# TEST_HJ-185.net
KiCad netlist of a schematic drawn in Altium Designer
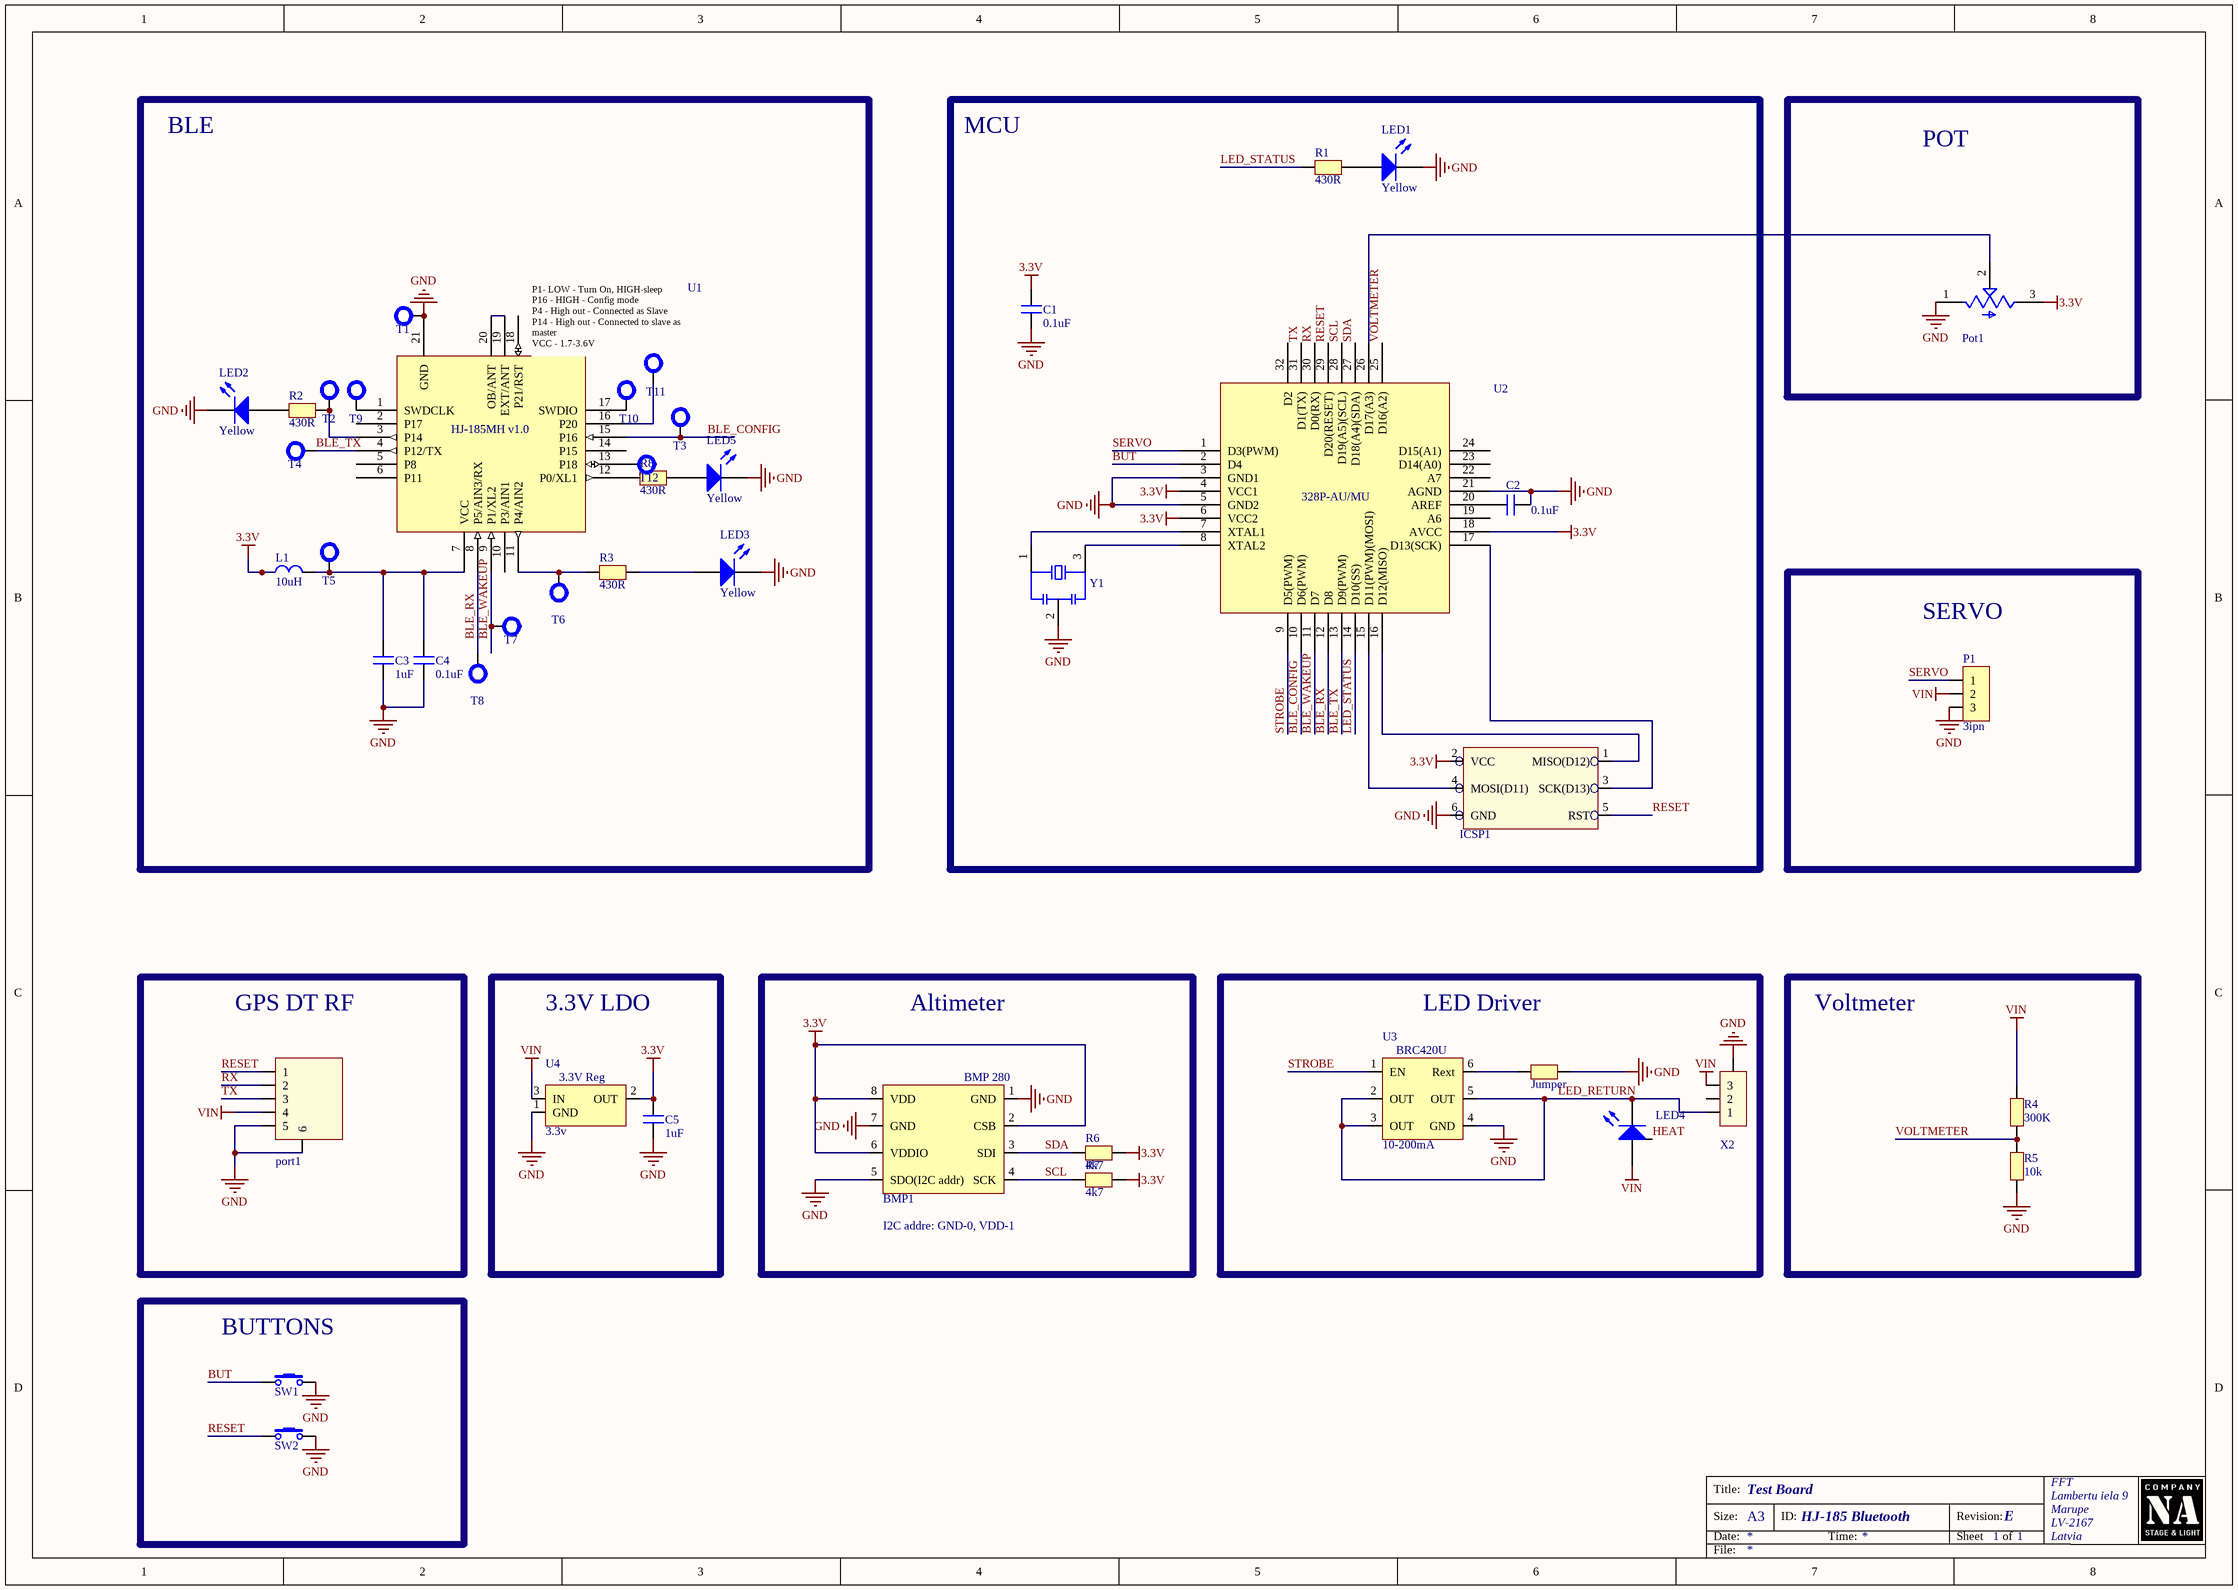
[diagram p0: TEST_HJ-185.SchDoc]

(export (version "E")
  (design (tool "Eeschema 10.0.6"))
  (components
    (comp (ref "BMP1")
      (value "± 0.12 hPa equivalent to ±1 m")
      (footprint "BMP280")
      (description "Pressure sensor")
      (fields (field (name "MANUFACTURER") "BOSCH") (field (name "PART NUMBER") "828-1064-1-ND - BMP 280"))
      (libsource (lib "My_Storage") (part "BMP 280"))
    )
    (comp (ref "C1")
      (value "0.1uF")
      (footprint "FFT:C0603-FFT")
      (description "C0603_0.1uF_50V")
      (fields (field (name "PART NUMBER") "CC0603KRX7R9BB104") (field (name "MANUFACTURER") "YAEGO"))
      (libsource (lib "LCSC") (part "C0603_0.1uF_50V"))
    )
    (comp (ref "C2")
      (value "0.1uF")
      (footprint "FFT:C0603-FFT")
      (description "C0603_0.1uF_50V")
      (fields (field (name "PART NUMBER") "CC0603KRX7R9BB104") (field (name "MANUFACTURER") "YAEGO"))
      (libsource (lib "LCSC") (part "C0603_0.1uF_50V"))
    )
    (comp (ref "C3")
      (value "1uF")
      (footprint "FFT:C0603-FFT")
      (description "C0603_1uF_25V")
      (fields (field (name "PART NUMBER") "CL10A105KB8NNNC") (field (name "MANUFACTURER") "SAMSUNG"))
      (libsource (lib "LCSC") (part "C0603_1uF_25V"))
    )
    (comp (ref "C4")
      (value "0.1uF")
      (footprint "FFT:C0603-FFT")
      (description "C0603_0.1uF_50V")
      (fields (field (name "PART NUMBER") "CC0603KRX7R9BB104") (field (name "MANUFACTURER") "YAEGO"))
      (libsource (lib "LCSC") (part "C0603_0.1uF_50V"))
    )
    (comp (ref "C5")
      (value "1uF")
      (footprint "FFT:C0603-FFT")
      (description "C0603_1uF_25V")
      (fields (field (name "PART NUMBER") "CL10A105KB8NNNC") (field (name "MANUFACTURER") "SAMSUNG"))
      (libsource (lib "LCSC") (part "C0603_1uF_25V"))
    )
    (comp (ref "ICSP1")
      (value "Progr ICSP")
      (footprint "ICSP prg PIN 2.54mm")
      (description "PAD prog")
      (libsource (lib "FFT") (part "Progr ICSP"))
    )
    (comp (ref "L1")
      (value "10uH")
      (footprint "FFT:L0603")
      (description "Inductor")
      (fields (field (name "PART NUMBER") "222") (field (name "MANUFACTURER") "Aliexpress"))
      (libsource (lib "FFT") (part "L0603_10uH"))
    )
    (comp (ref "LED1")
      (value "Yellow")
      (footprint "FFT:LED0603")
      (description "LED 0603 chip")
      (fields
        (field (name "MANUFACTURER") "Everlight Elec")
        (field (name "PART NUMBER") "19-213/Y2C-CQ2R2L/3T(CY)")
      )
      (libsource (lib "My_Storage") (part "19-213/Y2C-CQ2R2L/3T(CY)"))
    )
    (comp (ref "LED2")
      (value "Yellow")
      (footprint "FFT:LED0603")
      (description "LED 0603 chip")
      (fields
        (field (name "MANUFACTURER") "Everlight Elec")
        (field (name "PART NUMBER") "19-213/Y2C-CQ2R2L/3T(CY)")
      )
      (libsource (lib "My_Storage") (part "19-213/Y2C-CQ2R2L/3T(CY)"))
    )
    (comp (ref "LED3")
      (value "Yellow")
      (footprint "FFT:LED0603")
      (description "LED 0603 chip")
      (fields
        (field (name "MANUFACTURER") "Everlight Elec")
        (field (name "PART NUMBER") "19-213/Y2C-CQ2R2L/3T(CY)")
      )
      (libsource (lib "My_Storage") (part "19-213/Y2C-CQ2R2L/3T(CY)"))
    )
    (comp (ref "LED4")
      (value "Cool White")
      (footprint "CREE XPL")
      (description "LED")
      (fields (field (name "MANUFACTURER") "CREE") (field (name "PART NUMBER") "XPL"))
      (libsource (lib "FFT") (part "XPL"))
    )
    (comp (ref "LED5")
      (value "Yellow")
      (footprint "FFT:LED0603")
      (description "LED 0603 chip")
      (fields
        (field (name "MANUFACTURER") "Everlight Elec")
        (field (name "PART NUMBER") "19-213/Y2C-CQ2R2L/3T(CY)")
      )
      (libsource (lib "My_Storage") (part "19-213/Y2C-CQ2R2L/3T(CY)"))
    )
    (comp (ref "P1")
      (value "3ipn")
      (footprint "FFT:HDR1x3")
      (description "Header 3x1-PIN, 2.54mm")
      (fields (field (name "MANUFACTURER") "Connfly") (field (name "PART NUMBER") "DS1021-1*3SF1-1"))
      (libsource (lib "FFT") (part "Header 3x1"))
    )
    (comp (ref "port1")
      (value "1.0mm 5pin")
      (footprint "JST 5pin 1mm")
      (description "Connector 5p hor 1mm")
      (fields (field (name "MANUFACTURER") "JST") (field (name "PART NUMBER") "SM05B-SRSS-TB"))
      (libsource (lib "FFT") (part "SM05B-SRSS-TB"))
    )
    (comp (ref "Pot1")
      (value "TC33X-10K")
      (footprint "TrimPot - TC33X-2-101G")
      (description "TrimPot SMD")
      (fields (field (name "MANUFACTURER") "BOURNS"))
      (libsource (lib "My_Storage") (part "TC33X-10K"))
    )
    (comp (ref "R1")
      (value "430R")
      (footprint "FFT:R0603-FFT")
      (description "SMD resistor")
      (fields (field (name "PART NUMBER") "0603WAF4300T5E") (field (name "MANUFACTURER") "Uniroyal Elec"))
      (libsource (lib "") (part "R0603_430_2"))
    )
    (comp (ref "R2")
      (value "430R")
      (footprint "FFT:R0603-FFT")
      (description "SMD resistor")
      (fields (field (name "PART NUMBER") "0603WAF4300T5E") (field (name "MANUFACTURER") "Uniroyal Elec"))
      (libsource (lib "LCSC") (part "R0603_430"))
    )
    (comp (ref "R3")
      (value "430R")
      (footprint "FFT:R0603-FFT")
      (description "SMD resistor")
      (fields (field (name "PART NUMBER") "0603WAF4300T5E") (field (name "MANUFACTURER") "Uniroyal Elec"))
      (libsource (lib "") (part "R0603_430_2"))
    )
    (comp (ref "R4")
      (value "300K")
      (footprint "FFT:R0603-FFT")
      (description "SMD resistor")
      (fields (field (name "PART NUMBER") "0603WAF3003T5E") (field (name "MANUFACTURER") "Uniroyal Elec"))
      (libsource (lib "LCSC") (part "R0603_300k"))
    )
    (comp (ref "R5")
      (value "10k")
      (footprint "FFT:R0603-FFT")
      (description "SMD resistor")
      (fields (field (name "PART NUMBER") "0603WAF1002T5E") (field (name "MANUFACTURER") "Uniroyal Elec"))
      (libsource (lib "LCSC") (part "R0603_10k"))
    )
    (comp (ref "R6")
      (value "4k7")
      (footprint "FFT:R0603-FFT")
      (description "SMD resistor")
      (fields (field (name "PART NUMBER") "SMD0603-4K7-1%") (field (name "MANUFACTURER") "Yageo"))
      (libsource (lib "LCSC") (part "R0603_4k7"))
    )
    (comp (ref "R7")
      (value "4k7")
      (footprint "FFT:R0603-FFT")
      (description "SMD resistor")
      (fields (field (name "PART NUMBER") "SMD0603-4K7-1%") (field (name "MANUFACTURER") "Yageo"))
      (libsource (lib "LCSC") (part "R0603_4k7"))
    )
    (comp (ref "R8")
      (value "430R")
      (footprint "FFT:R0603-FFT")
      (description "SMD resistor")
      (fields (field (name "PART NUMBER") "0603WAF4300T5E") (field (name "MANUFACTURER") "Uniroyal Elec"))
      (libsource (lib "") (part "R0603_430_1"))
    )
    (comp (ref "SW1")
      (value "~")
      (footprint "Switch Tactile SKRPACE010")
      (description "Switch Tactile")
      (fields (field (name "MANUFACTURER") "ALPS") (field (name "PART NUMBER") "SKRPACE010"))
      (libsource (lib "My_Storage") (part "SKRPACE010"))
    )
    (comp (ref "SW2")
      (value "~")
      (footprint "Switch Tactile TS-1088C")
      (description "Switch Tactile")
      (fields (field (name "MANUFACTURER") "XUNPU") (field (name "PART NUMBER") "TS-1088C-02526"))
      (libsource (lib "My_Storage") (part "TS-1088C-02526"))
    )
    (comp (ref "T1")
      (value "?")
      (footprint "FFT:Test Point")
      (description "Test Point")
      (fields (field (name "PART NUMBER") "C0402"))
      (libsource (lib "FFT") (part "Test Point"))
    )
    (comp (ref "T2")
      (value "?")
      (footprint "FFT:Test Point")
      (description "Test Point")
      (fields (field (name "PART NUMBER") "C0402"))
      (libsource (lib "FFT") (part "Test Point"))
    )
    (comp (ref "T3")
      (value "?")
      (footprint "FFT:Test Point")
      (description "Test Point")
      (fields (field (name "PART NUMBER") "C0402"))
      (libsource (lib "FFT") (part "Test Point"))
    )
    (comp (ref "T4")
      (value "?")
      (footprint "FFT:Test Point")
      (description "Test Point")
      (fields (field (name "PART NUMBER") "C0402"))
      (libsource (lib "FFT") (part "Test Point"))
    )
    (comp (ref "T5")
      (value "?")
      (footprint "FFT:Test Point")
      (description "Test Point")
      (fields (field (name "PART NUMBER") "C0402"))
      (libsource (lib "FFT") (part "Test Point"))
    )
    (comp (ref "T6")
      (value "?")
      (footprint "FFT:Test Point")
      (description "Test Point")
      (fields (field (name "PART NUMBER") "C0402"))
      (libsource (lib "FFT") (part "Test Point"))
    )
    (comp (ref "T7")
      (value "?")
      (footprint "FFT:Test Point")
      (description "Test Point")
      (fields (field (name "PART NUMBER") "C0402"))
      (libsource (lib "FFT") (part "Test Point"))
    )
    (comp (ref "T8")
      (value "?")
      (footprint "FFT:Test Point")
      (description "Test Point")
      (fields (field (name "PART NUMBER") "C0402"))
      (libsource (lib "FFT") (part "Test Point"))
    )
    (comp (ref "T9")
      (value "?")
      (footprint "FFT:Test Point")
      (description "Test Point")
      (fields (field (name "PART NUMBER") "C0402"))
      (libsource (lib "FFT") (part "Test Point"))
    )
    (comp (ref "T10")
      (value "?")
      (footprint "FFT:Test Point")
      (description "Test Point")
      (fields (field (name "PART NUMBER") "C0402"))
      (libsource (lib "FFT") (part "Test Point"))
    )
    (comp (ref "T11")
      (value "?")
      (footprint "FFT:Test Point")
      (description "Test Point")
      (fields (field (name "PART NUMBER") "C0402"))
      (libsource (lib "FFT") (part "Test Point"))
    )
    (comp (ref "T12")
      (value "?")
      (footprint "FFT:Test Point")
      (description "Test Point")
      (fields (field (name "PART NUMBER") "C0402"))
      (libsource (lib "FFT") (part "Test Point"))
    )
    (comp (ref "U1")
      (value "~")
      (footprint "LGA-24-fft")
      (description "Module BLE")
      (fields (field (name "PART NUMBER") "HJ-185IMH_SPPv2") (field (name "MANUFACTURER") "tshjdz.com"))
      (libsource (lib "My_Storage") (part "HJ-185MH"))
    )
    (comp (ref "U2")
      (value "~")
      (footprint "32-pin QFP 10mm")
      (description "MCU")
      (fields (field (name "PART NUMBER") "ATmega 328p-AU") (field (name "MANUFACTURER") "Microchip Tech"))
      (libsource (lib "My_Storage") (part "Atmega 328P-AU"))
    )
    (comp (ref "U3")
      (value "10-200mA")
      (footprint "FFT:SC74")
      (description "LED Driver 10-200mA")
      (fields (field (name "MANUFACTURER") "Infeon") (field (name "PART NUMBER") "BCR421UE6327"))
      (libsource (lib "My_Storage") (part "BRC420U"))
    )
    (comp (ref "U4")
      (value "3.3v")
      (footprint "SOT23-3")
      (description "LDO 3.3V 300mA")
      (fields (field (name "PART NUMBER") "MIC5209") (field (name "MANUFACTURER") "DIODES INCORPORATED"))
      (libsource (lib "FFT") (part "AP2210N-3.3TRG1"))
    )
    (comp (ref "X1")
      (value "Jumper")
      (footprint "0603 clear pad")
      (description "Pad")
      (fields (field (name "PART NUMBER") "1212") (field (name "MANUFACTURER") "clear pad"))
      (libsource (lib "FFT") (part "Jumper 0603"))
    )
    (comp (ref "X2")
      (value "1.0mm 3pin")
      (footprint "JST 3pin 1mm")
      (description "Connector 3p hor 1mm")
      (fields (field (name "MANUFACTURER") "JST") (field (name "PART NUMBER") "SM05B-SRSS-TB"))
      (libsource (lib "My_Storage") (part "SM03B-SRSS-TB"))
    )
    (comp (ref "Y1")
      (value "CSTCE8M0V53-R0")
      (footprint "OSC_CSTCE16M0V53-R0")
      (description "Ceramic Resonator 8Mhz")
      (fields (field (name "MANUFACTURER") "Murata") (field (name "PART NUMBER") "CSTCE8M0V53-R0_1"))
      (libsource (lib "My_Storage") (part "CSTCE8M0V53-R0"))
    )
  )
  (nets
    (net (code "1") (name "/BLE_CONFIG") (class "Default")
      (node (ref "T3") (pin "1") (pintype "passive"))
      (node (ref "U1") (pin "15") (pinfunction "P16_15") (pintype "input"))
      (node (ref "U2") (pin "10") (pinfunction "D6(PWM)_10") (pintype "passive"))
    )
    (net (code "2") (name "/BLE_RX") (class "Default")
      (node (ref "T8") (pin "1") (pintype "passive"))
      (node (ref "U1") (pin "8") (pinfunction "P5/AIN3/RX_8") (pintype "input"))
      (node (ref "U2") (pin "12") (pinfunction "D8_12") (pintype "passive"))
    )
    (net (code "3") (name "/BLE_TX") (class "Default")
      (node (ref "T4") (pin "1") (pintype "passive"))
      (node (ref "U1") (pin "4") (pinfunction "P12/TX_4") (pintype "output"))
      (node (ref "U2") (pin "13") (pinfunction "D9(PWM)_13") (pintype "passive"))
    )
    (net (code "4") (name "/BLE_WAKEUP") (class "Default")
      (node (ref "T7") (pin "1") (pintype "passive"))
      (node (ref "U1") (pin "9") (pinfunction "P1/XL2_9") (pintype "input"))
      (node (ref "U2") (pin "11") (pinfunction "D7_11") (pintype "passive"))
    )
    (net (code "5") (name "/BUT") (class "Default")
      (node (ref "SW1") (pin "1") (pinfunction "1_1") (pintype "passive"))
      (node (ref "U2") (pin "2") (pinfunction "D4_2") (pintype "passive"))
    )
    (net (code "6") (name "/HEAT") (class "Default")
      (node (ref "LED4") (pin "PAD") (pinfunction "P_PAD") (pintype "passive"))
    )
    (net (code "7") (name "/LED_RETURN") (class "Default")
      (node (ref "LED4") (pin "K") (pinfunction "K_K") (pintype "passive"))
      (node (ref "U3") (pin "2") (pinfunction "OUT_2") (pintype "passive"))
      (node (ref "U3") (pin "3") (pinfunction "OUT_3") (pintype "passive"))
      (node (ref "U3") (pin "5") (pinfunction "OUT_5") (pintype "passive"))
      (node (ref "X2") (pin "1") (pinfunction "1_1") (pintype "passive"))
    )
    (net (code "8") (name "/LED_STATUS") (class "Default")
      (node (ref "R1") (pin "1") (pinfunction "1_1") (pintype "passive"))
      (node (ref "U2") (pin "14") (pinfunction "D10(SS)_14") (pintype "passive"))
    )
    (net (code "9") (name "/RESET") (class "Default")
      (node (ref "ICSP1") (pin "5") (pinfunction "RST_5") (pintype "passive"))
      (node (ref "SW2") (pin "1") (pinfunction "1_1") (pintype "passive"))
      (node (ref "U2") (pin "29") (pinfunction "D20(RESET)_29") (pintype "passive"))
      (node (ref "port1") (pin "1") (pinfunction "1_1") (pintype "passive"))
    )
    (net (code "10") (name "/RX") (class "Default")
      (node (ref "U2") (pin "30") (pinfunction "D0(RX)_30") (pintype "passive"))
      (node (ref "port1") (pin "2") (pinfunction "2_2") (pintype "passive"))
    )
    (net (code "11") (name "/SCL") (class "Default")
      (node (ref "BMP1") (pin "4") (pinfunction "SCK_4") (pintype "passive"))
      (node (ref "R7") (pin "1") (pinfunction "1_1") (pintype "passive"))
      (node (ref "U2") (pin "28") (pinfunction "D19(A5)(SCL)_28") (pintype "passive"))
    )
    (net (code "12") (name "/SDA") (class "Default")
      (node (ref "BMP1") (pin "3") (pinfunction "SDI_3") (pintype "passive"))
      (node (ref "R6") (pin "1") (pinfunction "1_1") (pintype "passive"))
      (node (ref "U2") (pin "27") (pinfunction "D18(A4)(SDA)_27") (pintype "passive"))
    )
    (net (code "13") (name "/SERVO") (class "Default")
      (node (ref "P1") (pin "1") (pinfunction "1_1") (pintype "passive"))
      (node (ref "U2") (pin "1") (pinfunction "D3(PWM)_1") (pintype "passive"))
    )
    (net (code "14") (name "/STROBE") (class "Default")
      (node (ref "U2") (pin "9") (pinfunction "D5(PWM)_9") (pintype "passive"))
      (node (ref "U3") (pin "1") (pinfunction "EN_1") (pintype "passive"))
    )
    (net (code "15") (name "/TX") (class "Default")
      (node (ref "U2") (pin "31") (pinfunction "D1(TX)_31") (pintype "passive"))
      (node (ref "port1") (pin "3") (pinfunction "3_3") (pintype "passive"))
    )
    (net (code "16") (name "/VOLTMETER") (class "Default")
      (node (ref "R4") (pin "1") (pinfunction "1_1") (pintype "passive"))
      (node (ref "R5") (pin "2") (pinfunction "2_2") (pintype "passive"))
      (node (ref "U2") (pin "25") (pinfunction "D16(A2)_25") (pintype "passive"))
    )
    (net (code "17") (name "3.3V") (class "Default")
      (node (ref "BMP1") (pin "2") (pinfunction "CSB_2") (pintype "passive"))
      (node (ref "BMP1") (pin "6") (pinfunction "VDDIO_6") (pintype "passive"))
      (node (ref "BMP1") (pin "8") (pinfunction "VDD_8") (pintype "passive"))
      (node (ref "C1") (pin "2") (pintype "passive"))
      (node (ref "C5") (pin "2") (pintype "passive"))
      (node (ref "ICSP1") (pin "2") (pinfunction "VCC_2") (pintype "passive"))
      (node (ref "L1") (pin "1") (pinfunction "1_1") (pintype "passive"))
      (node (ref "Pot1") (pin "3") (pinfunction "CW_3") (pintype "passive"))
      (node (ref "R6") (pin "2") (pinfunction "2_2") (pintype "passive"))
      (node (ref "R7") (pin "2") (pinfunction "2_2") (pintype "passive"))
      (node (ref "U2") (pin "18") (pinfunction "AVCC_18") (pintype "passive"))
      (node (ref "U2") (pin "4") (pinfunction "VCC1_4") (pintype "passive"))
      (node (ref "U2") (pin "6") (pinfunction "VCC2_6") (pintype "passive"))
      (node (ref "U4") (pin "2") (pinfunction "OUT_2") (pintype "passive"))
    )
    (net (code "18") (name "GND") (class "Default")
      (node (ref "BMP1") (pin "1") (pinfunction "GND_1") (pintype "passive"))
      (node (ref "BMP1") (pin "5") (pinfunction "SDO(I2C_addr)_5") (pintype "passive"))
      (node (ref "BMP1") (pin "7") (pinfunction "GND_7") (pintype "passive"))
      (node (ref "C1") (pin "1") (pintype "passive"))
      (node (ref "C2") (pin "2") (pintype "passive"))
      (node (ref "C3") (pin "1") (pintype "passive"))
      (node (ref "C4") (pin "1") (pintype "passive"))
      (node (ref "C5") (pin "1") (pintype "passive"))
      (node (ref "ICSP1") (pin "6") (pinfunction "GND_6") (pintype "passive"))
      (node (ref "LED1") (pin "C") (pinfunction "C_C") (pintype "passive"))
      (node (ref "LED2") (pin "C") (pinfunction "C_C") (pintype "passive"))
      (node (ref "LED3") (pin "C") (pinfunction "C_C") (pintype "passive"))
      (node (ref "LED5") (pin "C") (pinfunction "C_C") (pintype "passive"))
      (node (ref "P1") (pin "3") (pinfunction "3_3") (pintype "passive"))
      (node (ref "Pot1") (pin "1") (pinfunction "CCW_1") (pintype "passive"))
      (node (ref "R5") (pin "1") (pinfunction "1_1") (pintype "passive"))
      (node (ref "SW1") (pin "2") (pinfunction "2_2") (pintype "passive"))
      (node (ref "SW2") (pin "2") (pinfunction "2_2") (pintype "passive"))
      (node (ref "T1") (pin "1") (pintype "passive"))
      (node (ref "U1") (pin "21") (pinfunction "GND_21") (pintype "passive"))
      (node (ref "U2") (pin "21") (pinfunction "AGND_21") (pintype "passive"))
      (node (ref "U2") (pin "3") (pinfunction "GND1_3") (pintype "passive"))
      (node (ref "U2") (pin "5") (pinfunction "GND2_5") (pintype "passive"))
      (node (ref "U3") (pin "4") (pinfunction "GND_4") (pintype "passive"))
      (node (ref "U4") (pin "1") (pinfunction "GND_1") (pintype "power_in"))
      (node (ref "X1") (pin "1") (pintype "passive"))
      (node (ref "X2") (pin "6") (pinfunction "GND_6") (pintype "passive"))
      (node (ref "Y1") (pin "2") (pinfunction "OSC2_2") (pintype "passive"))
      (node (ref "port1") (pin "5") (pinfunction "5_5") (pintype "passive"))
      (node (ref "port1") (pin "6") (pinfunction "6_6") (pintype "passive"))
    )
    (net (code "19") (name "Net-(ICSP1-MISO(D12))") (class "Default")
      (node (ref "ICSP1") (pin "1") (pinfunction "MISO(D12)_1") (pintype "passive"))
      (node (ref "U2") (pin "16") (pinfunction "D12(MISO)_16") (pintype "passive"))
    )
    (net (code "20") (name "Net-(ICSP1-MOSI(D11))") (class "Default")
      (node (ref "ICSP1") (pin "4") (pinfunction "MOSI(D11)_4") (pintype "passive"))
      (node (ref "U2") (pin "15") (pinfunction "D11(PWM)(MOSI)_15") (pintype "passive"))
    )
    (net (code "21") (name "Net-(ICSP1-SCK(D13))") (class "Default")
      (node (ref "ICSP1") (pin "3") (pinfunction "SCK(D13)_3") (pintype "passive"))
      (node (ref "U2") (pin "17") (pinfunction "D13(SCK)_17") (pintype "passive"))
    )
    (net (code "22") (name "Net-(LED1-PadA)") (class "Default")
      (node (ref "LED1") (pin "A") (pinfunction "A_A") (pintype "passive"))
      (node (ref "R1") (pin "2") (pinfunction "2_2") (pintype "passive"))
    )
    (net (code "23") (name "Net-(LED2-PadA)") (class "Default")
      (node (ref "LED2") (pin "A") (pinfunction "A_A") (pintype "passive"))
      (node (ref "R2") (pin "2") (pinfunction "2_2") (pintype "passive"))
    )
    (net (code "24") (name "Net-(LED3-PadA)") (class "Default")
      (node (ref "LED3") (pin "A") (pinfunction "A_A") (pintype "passive"))
      (node (ref "R3") (pin "2") (pinfunction "2_2") (pintype "passive"))
    )
    (net (code "25") (name "Net-(LED5-PadA)") (class "Default")
      (node (ref "LED5") (pin "A") (pinfunction "A_A") (pintype "passive"))
      (node (ref "R8") (pin "2") (pinfunction "2_2") (pintype "passive"))
    )
    (net (code "26") (name "Net-(Pot1-W)") (class "Default")
      (node (ref "Pot1") (pin "2") (pinfunction "W_2") (pintype "passive"))
      (node (ref "U2") (pin "26") (pinfunction "D17(A3)_26") (pintype "passive"))
    )
    (net (code "27") (name "Net-(U1-EXT{slash}ANT)") (class "Default")
      (node (ref "U1") (pin "19") (pinfunction "EXT/ANT_19") (pintype "passive"))
      (node (ref "U1") (pin "20") (pinfunction "OB/ANT_20") (pintype "passive"))
    )
    (net (code "28") (name "Net-(U1-P0{slash}XL1)") (class "Default")
      (node (ref "R8") (pin "1") (pinfunction "1_1") (pintype "passive"))
      (node (ref "U1") (pin "12") (pinfunction "P0/XL1_12") (pintype "output"))
    )
    (net (code "29") (name "Net-(U1-P4{slash}AIN2)") (class "Default")
      (node (ref "R3") (pin "1") (pinfunction "1_1") (pintype "passive"))
      (node (ref "T6") (pin "1") (pintype "passive"))
      (node (ref "U1") (pin "11") (pinfunction "P4/AIN2_11") (pintype "output"))
    )
    (net (code "30") (name "Net-(U1-P14)") (class "Default")
      (node (ref "R2") (pin "1") (pinfunction "1_1") (pintype "passive"))
      (node (ref "T2") (pin "1") (pintype "passive"))
      (node (ref "U1") (pin "3") (pinfunction "P14_3") (pintype "output"))
    )
    (net (code "31") (name "Net-(U1-P18)") (class "Default")
      (node (ref "T12") (pin "1") (pintype "passive"))
      (node (ref "U1") (pin "13") (pinfunction "P18_13") (pintype "bidirectional"))
    )
    (net (code "32") (name "Net-(U1-P20)") (class "Default")
      (node (ref "T11") (pin "1") (pintype "passive"))
      (node (ref "U1") (pin "16") (pinfunction "P20_16") (pintype "passive"))
    )
    (net (code "33") (name "Net-(U1-SWDCLK)") (class "Default")
      (node (ref "T9") (pin "1") (pintype "passive"))
      (node (ref "U1") (pin "1") (pinfunction "SWDCLK_1") (pintype "passive"))
    )
    (net (code "34") (name "Net-(U1-SWDIO)") (class "Default")
      (node (ref "T10") (pin "1") (pintype "passive"))
      (node (ref "U1") (pin "17") (pinfunction "SWDIO_17") (pintype "passive"))
    )
    (net (code "35") (name "Net-(U1-VCC)") (class "Default")
      (node (ref "C3") (pin "2") (pintype "passive"))
      (node (ref "C4") (pin "2") (pintype "passive"))
      (node (ref "L1") (pin "2") (pinfunction "2_2") (pintype "passive"))
      (node (ref "T5") (pin "1") (pintype "passive"))
      (node (ref "U1") (pin "7") (pinfunction "VCC_7") (pintype "power_in"))
    )
    (net (code "36") (name "Net-(U2-AREF)") (class "Default")
      (node (ref "C2") (pin "1") (pintype "passive"))
      (node (ref "U2") (pin "20") (pinfunction "AREF_20") (pintype "passive"))
    )
    (net (code "37") (name "Net-(U2-XTAL1)") (class "Default")
      (node (ref "U2") (pin "7") (pinfunction "XTAL1_7") (pintype "passive"))
      (node (ref "Y1") (pin "1") (pinfunction "OSC1_1") (pintype "passive"))
    )
    (net (code "38") (name "Net-(U2-XTAL2)") (class "Default")
      (node (ref "U2") (pin "8") (pinfunction "XTAL2_8") (pintype "passive"))
      (node (ref "Y1") (pin "3") (pinfunction "OSC3_3") (pintype "passive"))
    )
    (net (code "39") (name "Net-(U3-Rext)") (class "Default")
      (node (ref "U3") (pin "6") (pinfunction "Rext_6") (pintype "passive"))
      (node (ref "X1") (pin "2") (pintype "passive"))
    )
    (net (code "40") (name "VIN") (class "Default")
      (node (ref "LED4") (pin "A") (pinfunction "A_A") (pintype "passive"))
      (node (ref "P1") (pin "2") (pinfunction "2_2") (pintype "passive"))
      (node (ref "R4") (pin "2") (pinfunction "2_2") (pintype "passive"))
      (node (ref "U4") (pin "3") (pinfunction "IN_3") (pintype "power_in"))
      (node (ref "X2") (pin "3") (pinfunction "3_3") (pintype "passive"))
      (node (ref "port1") (pin "4") (pinfunction "4_4") (pintype "passive"))
    )
    (net (code "41") (name "unconnected-(U1-P3{slash}AIN1-Pad10)") (class "Default")
      (node (ref "U1") (pin "10") (pinfunction "P3/AIN1_10") (pintype "passive"))
    )
    (net (code "42") (name "unconnected-(U1-P8-Pad5)") (class "Default")
      (node (ref "U1") (pin "5") (pinfunction "P8_5") (pintype "passive"))
    )
    (net (code "43") (name "unconnected-(U1-P11-Pad6)") (class "Default")
      (node (ref "U1") (pin "6") (pinfunction "P11_6") (pintype "passive"))
    )
    (net (code "44") (name "unconnected-(U1-P15-Pad14)") (class "Default")
      (node (ref "U1") (pin "14") (pinfunction "P15_14") (pintype "passive"))
    )
    (net (code "45") (name "unconnected-(U1-P17-Pad2)") (class "Default")
      (node (ref "U1") (pin "2") (pinfunction "P17_2") (pintype "passive"))
    )
    (net (code "46") (name "unconnected-(U1-P21{slash}RST-Pad18)") (class "Default")
      (node (ref "U1") (pin "18") (pinfunction "P21/RST_18") (pintype "bidirectional"))
    )
    (net (code "47") (name "unconnected-(U2-A6-Pad19)") (class "Default")
      (node (ref "U2") (pin "19") (pinfunction "A6_19") (pintype "passive"))
    )
    (net (code "48") (name "unconnected-(U2-A7-Pad22)") (class "Default")
      (node (ref "U2") (pin "22") (pinfunction "A7_22") (pintype "passive"))
    )
    (net (code "49") (name "unconnected-(U2-D2-Pad32)") (class "Default")
      (node (ref "U2") (pin "32") (pinfunction "D2_32") (pintype "passive"))
    )
    (net (code "50") (name "unconnected-(U2-D14(A0)-Pad23)") (class "Default")
      (node (ref "U2") (pin "23") (pinfunction "D14(A0)_23") (pintype "passive"))
    )
    (net (code "51") (name "unconnected-(U2-D15(A1)-Pad24)") (class "Default")
      (node (ref "U2") (pin "24") (pinfunction "D15(A1)_24") (pintype "passive"))
    )
    (net (code "52") (name "unconnected-(X2-Pad2)") (class "Default")
      (node (ref "X2") (pin "2") (pinfunction "2_2") (pintype "passive"))
    )
  )
)
